# CO2_sensor_v1_1_print.net
KiCad netlist of a schematic drawn in EAGLE
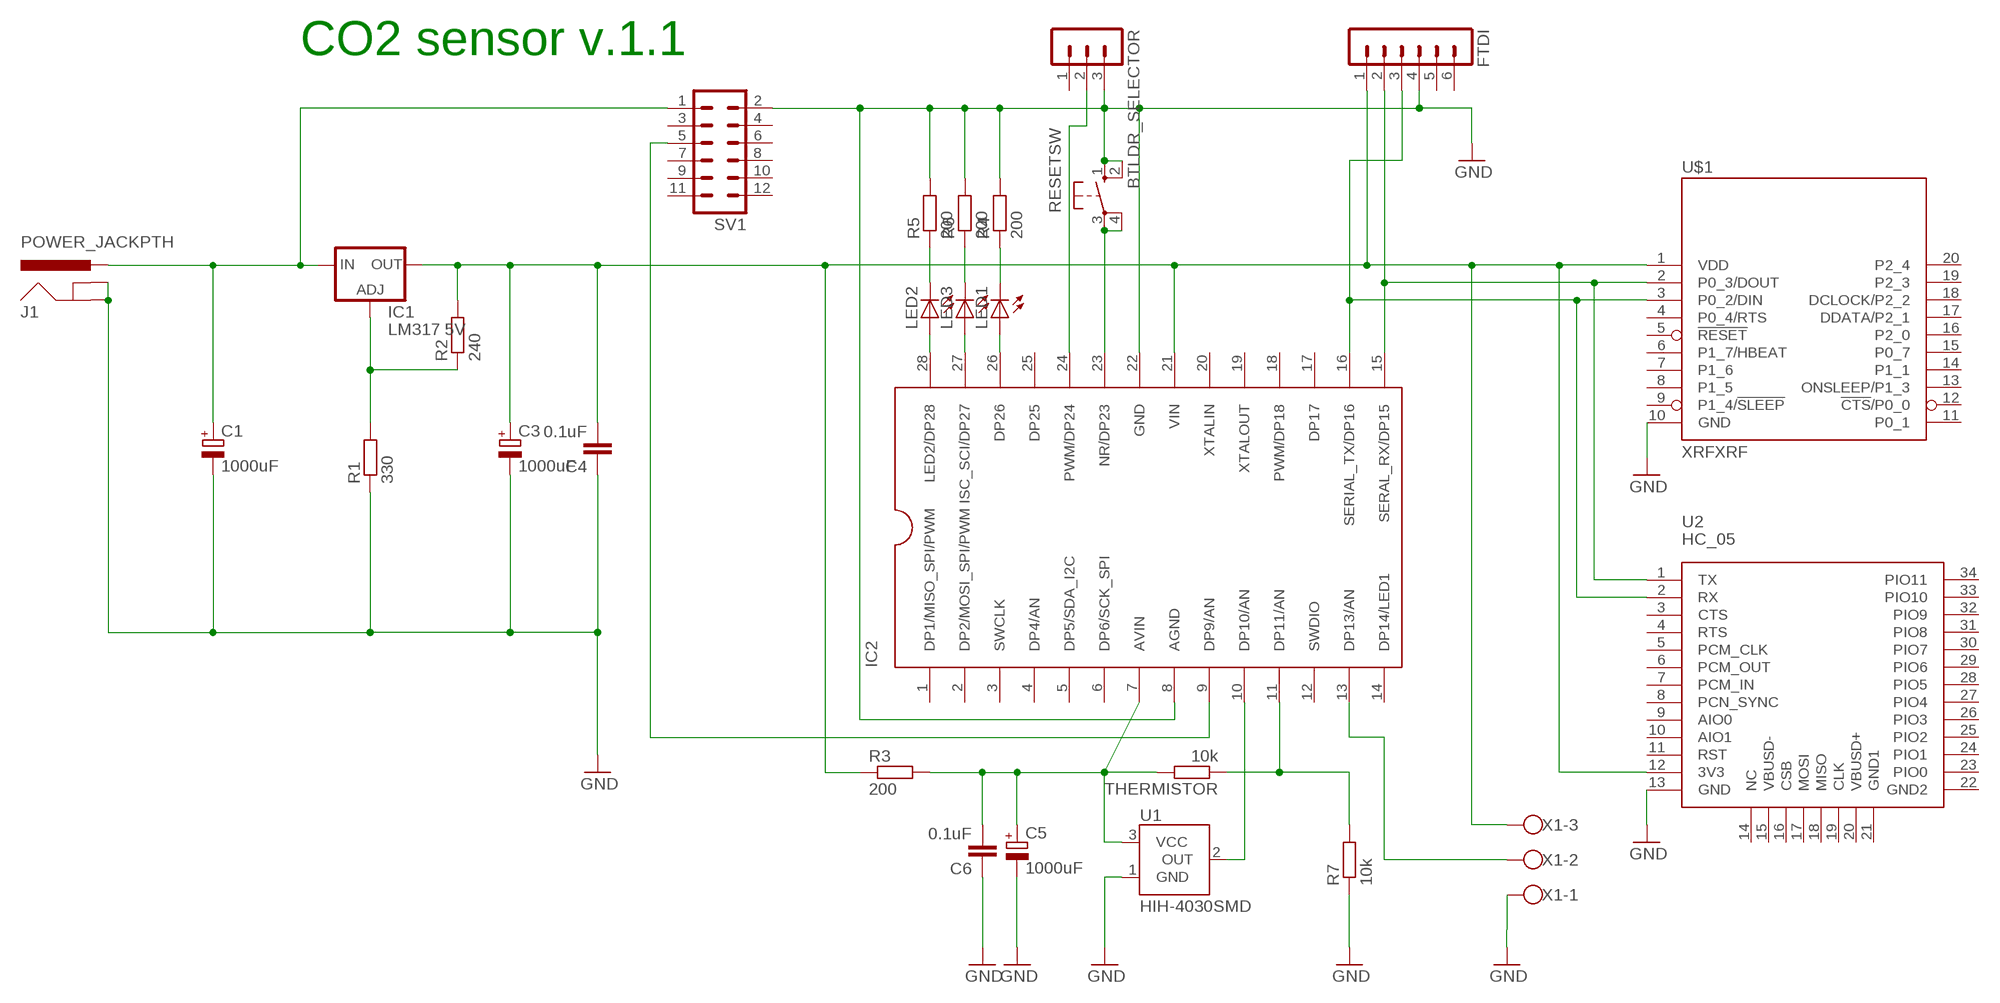
[diagram p0: schematic, sheet 1]

(export (version "E")
  (design (tool "Eeschema 10.0.6"))
  (components
    (comp (ref "BTLDR_SELECTOR")
      (value "MA03-1")
      (footprint "eagle-import:MA03-1")
      (libsource (lib "eagle-import") (part "MA03-1"))
    )
    (comp (ref "C1")
      (value "1000uF")
      (footprint "eagle-import:E5-10,5")
      (libsource (lib "eagle-import") (part "CPOL-EUE5-10.5"))
    )
    (comp (ref "C3")
      (value "1000uF")
      (footprint "eagle-import:E5-10,5")
      (libsource (lib "eagle-import") (part "CPOL-EUE5-10.5"))
    )
    (comp (ref "C4")
      (value "0.1uF")
      (footprint "eagle-import:C050-025X075")
      (libsource (lib "eagle-import") (part "C-EU050-025X075"))
    )
    (comp (ref "C5")
      (value "1000uF")
      (footprint "eagle-import:E5-10,5")
      (libsource (lib "eagle-import") (part "CPOL-EUE5-10.5"))
    )
    (comp (ref "C6")
      (value "0.1uF")
      (footprint "eagle-import:C050-025X075")
      (libsource (lib "eagle-import") (part "C-EU050-025X075"))
    )
    (comp (ref "FTDI")
      (value "MA06-1")
      (footprint "eagle-import:MA06-1")
      (libsource (lib "eagle-import") (part "MA06-1"))
    )
    (comp (ref "IC1")
      (value "LM317 5V")
      (footprint "eagle-import:317TL")
      (libsource (lib "eagle-import") (part "LM317TL"))
    )
    (comp (ref "IC2")
      (value "LPC1114FN28")
      (footprint "eagle-import:DIP28")
      (libsource (lib "eagle-import") (part "LPC1114FN28"))
    )
    (comp (ref "J1")
      (value "POWER_JACKPTH")
      (footprint "eagle-import:POWER_JACK_PTH")
      (libsource (lib "eagle-import") (part "POWER_JACKPTH"))
    )
    (comp (ref "LED1")
      (value "LED3MM")
      (footprint "eagle-import:LED3MM")
      (libsource (lib "eagle-import") (part "LED3MM"))
    )
    (comp (ref "LED2")
      (value "LED3MM")
      (footprint "eagle-import:LED3MM")
      (libsource (lib "eagle-import") (part "LED3MM"))
    )
    (comp (ref "LED3")
      (value "LED3MM")
      (footprint "eagle-import:LED3MM")
      (libsource (lib "eagle-import") (part "LED3MM"))
    )
    (comp (ref "R1")
      (value "330")
      (footprint "eagle-import:0207_10")
      (libsource (lib "eagle-import") (part "R-EU_0207/10"))
    )
    (comp (ref "R2")
      (value "240")
      (footprint "eagle-import:0207_12")
      (libsource (lib "eagle-import") (part "R-EU_0207/12"))
    )
    (comp (ref "R3")
      (value "200")
      (footprint "eagle-import:0207_12")
      (libsource (lib "eagle-import") (part "R-EU_0207/12"))
    )
    (comp (ref "R4")
      (value "200")
      (footprint "eagle-import:0207_10")
      (libsource (lib "eagle-import") (part "R-EU_0207/10"))
    )
    (comp (ref "R5")
      (value "200")
      (footprint "eagle-import:0207_2V")
      (libsource (lib "eagle-import") (part "R-EU_0207/2V"))
    )
    (comp (ref "R6")
      (value "200")
      (footprint "eagle-import:0207_12")
      (libsource (lib "eagle-import") (part "R-EU_0207/12"))
    )
    (comp (ref "R7")
      (value "10k")
      (footprint "eagle-import:0207_12")
      (libsource (lib "eagle-import") (part "R-EU_0207/12"))
    )
    (comp (ref "RESETSW")
      (value "10-XX")
      (footprint "eagle-import:B3F-10XX")
      (fields (field (name "MPN") "B3F-1000"))
      (libsource (lib "eagle-import") (part "10-XX"))
    )
    (comp (ref "SV1")
      (value "MA06-2")
      (footprint "eagle-import:MA06-2")
      (libsource (lib "eagle-import") (part "MA06-2"))
    )
    (comp (ref "THERMISTOR")
      (value "10k")
      (footprint "eagle-import:0207_5V")
      (libsource (lib "eagle-import") (part "R-EU_0207/5V"))
    )
    (comp (ref "U$1")
      (value "XRFXRF")
      (footprint "eagle-import:XRF")
      (libsource (lib "eagle-import") (part "XRFXRF"))
    )
    (comp (ref "U1")
      (value "HIH-4030SMD")
      (footprint "eagle-import:HIH-4030")
      (libsource (lib "eagle-import") (part "HIH-4030SMD"))
    )
    (comp (ref "U2")
      (value "HC_05")
      (footprint "eagle-import:BLUETOOTH_SMD")
      (libsource (lib "eagle-import") (part "HC_05"))
    )
    (comp (ref "X1")
      (value "W237-103")
      (footprint "eagle-import:W237-103")
      (fields (field (name "MPN") "237-103"))
      (libsource (lib "eagle-import") (part "W237-103"))
    )
  )
  (nets
    (net (code "1") (name "GND") (class "Default")
      (node (ref "BTLDR_SELECTOR") (pin "3") (pinfunction "3_3") (pintype "passive"))
      (node (ref "C1") (pin "-") (pinfunction "-_-") (pintype "passive"))
      (node (ref "C3") (pin "-") (pinfunction "-_-") (pintype "passive"))
      (node (ref "C4") (pin "1") (pinfunction "1_1") (pintype "passive"))
      (node (ref "C5") (pin "-") (pinfunction "-_-") (pintype "passive"))
      (node (ref "C6") (pin "1") (pinfunction "1_1") (pintype "passive"))
      (node (ref "FTDI") (pin "4") (pinfunction "4_4") (pintype "passive"))
      (node (ref "IC2") (pin "22") (pinfunction "GND_22") (pintype "power_in"))
      (node (ref "IC2") (pin "8") (pinfunction "AGND_8") (pintype "power_in"))
      (node (ref "J1") (pin "GND") (pinfunction "GND_GND") (pintype "bidirectional"))
      (node (ref "J1") (pin "GNDBREAK") (pinfunction "GNDBREAK_GNDBREAK") (pintype "bidirectional"))
      (node (ref "R1") (pin "1") (pinfunction "1_1") (pintype "passive"))
      (node (ref "R4") (pin "2") (pinfunction "2_2") (pintype "passive"))
      (node (ref "R5") (pin "2") (pinfunction "2_2") (pintype "passive"))
      (node (ref "R6") (pin "2") (pinfunction "2_2") (pintype "passive"))
      (node (ref "R7") (pin "1") (pinfunction "1_1") (pintype "passive"))
      (node (ref "RESETSW") (pin "1") (pinfunction "S_1") (pintype "passive"))
      (node (ref "RESETSW") (pin "2") (pinfunction "S1_2") (pintype "passive"))
      (node (ref "SV1") (pin "2") (pinfunction "2_2") (pintype "passive"))
      (node (ref "U$1") (pin "10") (pinfunction "GND_10") (pintype "power_in"))
      (node (ref "U1") (pin "1") (pinfunction "GND_1") (pintype "bidirectional"))
      (node (ref "U2") (pin "13") (pinfunction "GND_13") (pintype "bidirectional"))
      (node (ref "X1") (pin "1") (pinfunction "KL_1") (pintype "passive"))
    )
    (net (code "2") (name "Net-(IC1-ADJ)") (class "Default")
      (node (ref "IC1") (pin "1") (pinfunction "ADJ_1") (pintype "input"))
      (node (ref "R1") (pin "2") (pinfunction "2_2") (pintype "passive"))
      (node (ref "R2") (pin "1") (pinfunction "1_1") (pintype "passive"))
    )
    (net (code "3") (name "Net-(IC1-IN)") (class "Default")
      (node (ref "C1") (pin "+") (pinfunction "+_+") (pintype "passive"))
      (node (ref "IC1") (pin "3") (pinfunction "IN_3") (pintype "input"))
      (node (ref "J1") (pin "PWR") (pinfunction "PWR_PWR") (pintype "bidirectional"))
      (node (ref "SV1") (pin "1") (pinfunction "1_1") (pintype "passive"))
    )
    (net (code "4") (name "Net-(IC1-OUT)") (class "Default")
      (node (ref "C3") (pin "+") (pinfunction "+_+") (pintype "passive"))
      (node (ref "C4") (pin "2") (pinfunction "2_2") (pintype "passive"))
      (node (ref "FTDI") (pin "1") (pinfunction "1_1") (pintype "passive"))
      (node (ref "IC1") (pin "2") (pinfunction "OUT_2") (pintype "passive"))
      (node (ref "IC2") (pin "21") (pinfunction "VIN_21") (pintype "power_in"))
      (node (ref "R2") (pin "2") (pinfunction "2_2") (pintype "passive"))
      (node (ref "R3") (pin "1") (pinfunction "1_1") (pintype "passive"))
      (node (ref "U$1") (pin "1") (pinfunction "VDD_1") (pintype "power_in"))
      (node (ref "U2") (pin "12") (pinfunction "3V3_12") (pintype "bidirectional"))
      (node (ref "X1") (pin "3") (pinfunction "KL_3") (pintype "passive"))
    )
    (net (code "5") (name "Net-(IC2-AVIN)") (class "Default")
      (node (ref "C5") (pin "+") (pinfunction "+_+") (pintype "passive"))
      (node (ref "C6") (pin "2") (pinfunction "2_2") (pintype "passive"))
      (node (ref "IC2") (pin "7") (pinfunction "AVIN_7") (pintype "power_in"))
      (node (ref "R3") (pin "2") (pinfunction "2_2") (pintype "passive"))
      (node (ref "THERMISTOR") (pin "2") (pinfunction "2_2") (pintype "passive"))
      (node (ref "U1") (pin "3") (pinfunction "VCC_3") (pintype "bidirectional"))
    )
    (net (code "6") (name "Net-(IC2-DP9{slash}AN)") (class "Default")
      (node (ref "IC2") (pin "9") (pinfunction "DP9/AN_9") (pintype "bidirectional"))
      (node (ref "SV1") (pin "5") (pinfunction "5_5") (pintype "passive"))
    )
    (net (code "7") (name "Net-(IC2-DP10{slash}AN)") (class "Default")
      (node (ref "IC2") (pin "10") (pinfunction "DP10/AN_10") (pintype "bidirectional"))
      (node (ref "U1") (pin "2") (pinfunction "OUT_2") (pintype "bidirectional"))
    )
    (net (code "8") (name "Net-(IC2-DP11{slash}AN)") (class "Default")
      (node (ref "IC2") (pin "11") (pinfunction "DP11/AN_11") (pintype "bidirectional"))
      (node (ref "R7") (pin "2") (pinfunction "2_2") (pintype "passive"))
      (node (ref "THERMISTOR") (pin "1") (pinfunction "1_1") (pintype "passive"))
    )
    (net (code "9") (name "Net-(IC2-DP13{slash}AN)") (class "Default")
      (node (ref "IC2") (pin "13") (pinfunction "DP13/AN_13") (pintype "bidirectional"))
      (node (ref "X1") (pin "2") (pinfunction "KL_2") (pintype "passive"))
    )
    (net (code "10") (name "Net-(IC2-DP26)") (class "Default")
      (node (ref "IC2") (pin "26") (pinfunction "DP26_26") (pintype "bidirectional"))
      (node (ref "LED1") (pin "A") (pinfunction "A_A") (pintype "passive"))
    )
    (net (code "11") (name "Net-(IC2-ISC_SCI{slash}DP27)") (class "Default")
      (node (ref "IC2") (pin "27") (pinfunction "ISC_SCI/DP27_27") (pintype "bidirectional"))
      (node (ref "LED3") (pin "A") (pinfunction "A_A") (pintype "passive"))
    )
    (net (code "12") (name "Net-(IC2-LED2{slash}DP28)") (class "Default")
      (node (ref "IC2") (pin "28") (pinfunction "LED2/DP28_28") (pintype "bidirectional"))
      (node (ref "LED2") (pin "A") (pinfunction "A_A") (pintype "passive"))
    )
    (net (code "13") (name "Net-(IC2-NR{slash}DP23)") (class "Default")
      (node (ref "IC2") (pin "23") (pinfunction "NR/DP23_23") (pintype "bidirectional"))
      (node (ref "RESETSW") (pin "3") (pinfunction "P_3") (pintype "passive"))
      (node (ref "RESETSW") (pin "4") (pinfunction "P1_4") (pintype "passive"))
    )
    (net (code "14") (name "Net-(IC2-PWM{slash}DP24)") (class "Default")
      (node (ref "BTLDR_SELECTOR") (pin "2") (pinfunction "2_2") (pintype "passive"))
      (node (ref "IC2") (pin "24") (pinfunction "PWM/DP24_24") (pintype "bidirectional"))
    )
    (net (code "15") (name "Net-(IC2-SERAL_RX{slash}DP15)") (class "Default")
      (node (ref "FTDI") (pin "2") (pinfunction "2_2") (pintype "passive"))
      (node (ref "IC2") (pin "15") (pinfunction "SERAL_RX/DP15_15") (pintype "bidirectional"))
      (node (ref "U$1") (pin "2") (pinfunction "P0_3/DOUT_2") (pintype "output"))
      (node (ref "U2") (pin "1") (pinfunction "TX_1") (pintype "bidirectional"))
    )
    (net (code "16") (name "Net-(IC2-SERIAL_TX{slash}DP16)") (class "Default")
      (node (ref "FTDI") (pin "3") (pinfunction "3_3") (pintype "passive"))
      (node (ref "IC2") (pin "16") (pinfunction "SERIAL_TX/DP16_16") (pintype "bidirectional"))
      (node (ref "U$1") (pin "3") (pinfunction "P0_2/DIN_3") (pintype "input"))
      (node (ref "U2") (pin "2") (pinfunction "RX_2") (pintype "bidirectional"))
    )
    (net (code "17") (name "Net-(LED1-C)") (class "Default")
      (node (ref "LED1") (pin "K") (pinfunction "C_K") (pintype "passive"))
      (node (ref "R4") (pin "1") (pinfunction "1_1") (pintype "passive"))
    )
    (net (code "18") (name "Net-(LED2-C)") (class "Default")
      (node (ref "LED2") (pin "K") (pinfunction "C_K") (pintype "passive"))
      (node (ref "R5") (pin "1") (pinfunction "1_1") (pintype "passive"))
    )
    (net (code "19") (name "Net-(LED3-C)") (class "Default")
      (node (ref "LED3") (pin "K") (pinfunction "C_K") (pintype "passive"))
      (node (ref "R6") (pin "1") (pinfunction "1_1") (pintype "passive"))
    )
    (net (code "20") (name "unconnected-(BTLDR_SELECTOR-Pad1)") (class "Default")
      (node (ref "BTLDR_SELECTOR") (pin "1") (pinfunction "1_1") (pintype "passive"))
    )
    (net (code "21") (name "unconnected-(FTDI-Pad5)") (class "Default")
      (node (ref "FTDI") (pin "5") (pinfunction "5_5") (pintype "passive"))
    )
    (net (code "22") (name "unconnected-(FTDI-Pad6)") (class "Default")
      (node (ref "FTDI") (pin "6") (pinfunction "6_6") (pintype "passive"))
    )
    (net (code "23") (name "unconnected-(IC2-DP1{slash}MISO_SPI{slash}PWM-Pad1)") (class "Default")
      (node (ref "IC2") (pin "1") (pinfunction "DP1/MISO_SPI/PWM_1") (pintype "bidirectional"))
    )
    (net (code "24") (name "unconnected-(IC2-DP2{slash}MOSI_SPI{slash}PWM-Pad2)") (class "Default")
      (node (ref "IC2") (pin "2") (pinfunction "DP2/MOSI_SPI/PWM_2") (pintype "bidirectional"))
    )
    (net (code "25") (name "unconnected-(IC2-DP4{slash}AN-Pad4)") (class "Default")
      (node (ref "IC2") (pin "4") (pinfunction "DP4/AN_4") (pintype "bidirectional"))
    )
    (net (code "26") (name "unconnected-(IC2-DP5{slash}SDA_I2C-Pad5)") (class "Default")
      (node (ref "IC2") (pin "5") (pinfunction "DP5/SDA_I2C_5") (pintype "bidirectional"))
    )
    (net (code "27") (name "unconnected-(IC2-DP6{slash}SCK_SPI-Pad6)") (class "Default")
      (node (ref "IC2") (pin "6") (pinfunction "DP6/SCK_SPI_6") (pintype "bidirectional"))
    )
    (net (code "28") (name "unconnected-(IC2-DP14{slash}LED1-Pad14)") (class "Default")
      (node (ref "IC2") (pin "14") (pinfunction "DP14/LED1_14") (pintype "bidirectional"))
    )
    (net (code "29") (name "unconnected-(IC2-DP17-Pad17)") (class "Default")
      (node (ref "IC2") (pin "17") (pinfunction "DP17_17") (pintype "bidirectional"))
    )
    (net (code "30") (name "unconnected-(IC2-DP25-Pad25)") (class "Default")
      (node (ref "IC2") (pin "25") (pinfunction "DP25_25") (pintype "bidirectional"))
    )
    (net (code "31") (name "unconnected-(IC2-PWM{slash}DP18-Pad18)") (class "Default")
      (node (ref "IC2") (pin "18") (pinfunction "PWM/DP18_18") (pintype "bidirectional"))
    )
    (net (code "32") (name "unconnected-(IC2-SWCLK-Pad3)") (class "Default")
      (node (ref "IC2") (pin "3") (pinfunction "SWCLK_3") (pintype "bidirectional"))
    )
    (net (code "33") (name "unconnected-(IC2-SWDIO-Pad12)") (class "Default")
      (node (ref "IC2") (pin "12") (pinfunction "SWDIO_12") (pintype "bidirectional"))
    )
    (net (code "34") (name "unconnected-(IC2-XTALIN-Pad20)") (class "Default")
      (node (ref "IC2") (pin "20") (pinfunction "XTALIN_20") (pintype "input"))
    )
    (net (code "35") (name "unconnected-(IC2-XTALOUT-Pad19)") (class "Default")
      (node (ref "IC2") (pin "19") (pinfunction "XTALOUT_19") (pintype "output"))
    )
    (net (code "36") (name "unconnected-(SV1-Pad3)") (class "Default")
      (node (ref "SV1") (pin "3") (pinfunction "3_3") (pintype "passive"))
    )
    (net (code "37") (name "unconnected-(SV1-Pad4)") (class "Default")
      (node (ref "SV1") (pin "4") (pinfunction "4_4") (pintype "passive"))
    )
    (net (code "38") (name "unconnected-(SV1-Pad6)") (class "Default")
      (node (ref "SV1") (pin "6") (pinfunction "6_6") (pintype "passive"))
    )
    (net (code "39") (name "unconnected-(SV1-Pad7)") (class "Default")
      (node (ref "SV1") (pin "7") (pinfunction "7_7") (pintype "passive"))
    )
    (net (code "40") (name "unconnected-(SV1-Pad8)") (class "Default")
      (node (ref "SV1") (pin "8") (pinfunction "8_8") (pintype "passive"))
    )
    (net (code "41") (name "unconnected-(SV1-Pad9)") (class "Default")
      (node (ref "SV1") (pin "9") (pinfunction "9_9") (pintype "passive"))
    )
    (net (code "42") (name "unconnected-(SV1-Pad10)") (class "Default")
      (node (ref "SV1") (pin "10") (pinfunction "10_10") (pintype "passive"))
    )
    (net (code "43") (name "unconnected-(SV1-Pad11)") (class "Default")
      (node (ref "SV1") (pin "11") (pinfunction "11_11") (pintype "passive"))
    )
    (net (code "44") (name "unconnected-(SV1-Pad12)") (class "Default")
      (node (ref "SV1") (pin "12") (pinfunction "12_12") (pintype "passive"))
    )
    (net (code "45") (name "unconnected-(U$1-DCLOCK{slash}P2_2-Pad18)") (class "Default")
      (node (ref "U$1") (pin "18") (pinfunction "DCLOCK/P2_2_18") (pintype "bidirectional"))
    )
    (net (code "46") (name "unconnected-(U$1-DDATA{slash}P2_1-Pad17)") (class "Default")
      (node (ref "U$1") (pin "17") (pinfunction "DDATA/P2_1_17") (pintype "bidirectional"))
    )
    (net (code "47") (name "unconnected-(U$1-ONSLEEP{slash}P1_3-Pad13)") (class "Default")
      (node (ref "U$1") (pin "13") (pinfunction "ONSLEEP/P1_3_13") (pintype "bidirectional"))
    )
    (net (code "48") (name "unconnected-(U$1-P0_1-Pad11)") (class "Default")
      (node (ref "U$1") (pin "11") (pinfunction "P0_1_11") (pintype "bidirectional"))
    )
    (net (code "49") (name "unconnected-(U$1-P0_4{slash}RTS-Pad4)") (class "Default")
      (node (ref "U$1") (pin "4") (pinfunction "P0_4/RTS_4") (pintype "bidirectional"))
    )
    (net (code "50") (name "unconnected-(U$1-P0_7-Pad15)") (class "Default")
      (node (ref "U$1") (pin "15") (pinfunction "P0_7_15") (pintype "bidirectional"))
    )
    (net (code "51") (name "unconnected-(U$1-P1_1-Pad14)") (class "Default")
      (node (ref "U$1") (pin "14") (pinfunction "P1_1_14") (pintype "bidirectional"))
    )
    (net (code "52") (name "unconnected-(U$1-P1_4{slash}~{SLEEP}-Pad9)") (class "Default")
      (node (ref "U$1") (pin "9") (pinfunction "P1_4/~{SLEEP}_9") (pintype "bidirectional"))
    )
    (net (code "53") (name "unconnected-(U$1-P1_5-Pad8)") (class "Default")
      (node (ref "U$1") (pin "8") (pinfunction "P1_5_8") (pintype "bidirectional"))
    )
    (net (code "54") (name "unconnected-(U$1-P1_6-Pad7)") (class "Default")
      (node (ref "U$1") (pin "7") (pinfunction "P1_6_7") (pintype "bidirectional"))
    )
    (net (code "55") (name "unconnected-(U$1-P1_7{slash}HBEAT-Pad6)") (class "Default")
      (node (ref "U$1") (pin "6") (pinfunction "P1_7/HBEAT_6") (pintype "bidirectional"))
    )
    (net (code "56") (name "unconnected-(U$1-P2_0-Pad16)") (class "Default")
      (node (ref "U$1") (pin "16") (pinfunction "P2_0_16") (pintype "input"))
    )
    (net (code "57") (name "unconnected-(U$1-P2_3-Pad19)") (class "Default")
      (node (ref "U$1") (pin "19") (pinfunction "P2_3_19") (pintype "bidirectional"))
    )
    (net (code "58") (name "unconnected-(U$1-P2_4-Pad20)") (class "Default")
      (node (ref "U$1") (pin "20") (pinfunction "P2_4_20") (pintype "bidirectional"))
    )
    (net (code "59") (name "unconnected-(U$1-~{CTS}{slash}P0_0-Pad12)") (class "Default")
      (node (ref "U$1") (pin "12") (pinfunction "~{CTS}/P0_0_12") (pintype "output"))
    )
    (net (code "60") (name "unconnected-(U$1-~{RESET}-Pad5)") (class "Default")
      (node (ref "U$1") (pin "5") (pinfunction "~{RESET}_5") (pintype "input"))
    )
    (net (code "61") (name "unconnected-(U2-AIO0-Pad9)") (class "Default")
      (node (ref "U2") (pin "9") (pinfunction "AIO0_9") (pintype "bidirectional"))
    )
    (net (code "62") (name "unconnected-(U2-AIO1-Pad10)") (class "Default")
      (node (ref "U2") (pin "10") (pinfunction "AIO1_10") (pintype "bidirectional"))
    )
    (net (code "63") (name "unconnected-(U2-CLK-Pad19)") (class "Default")
      (node (ref "U2") (pin "19") (pinfunction "CLK_19") (pintype "bidirectional"))
    )
    (net (code "64") (name "unconnected-(U2-CSB-Pad16)") (class "Default")
      (node (ref "U2") (pin "16") (pinfunction "CSB_16") (pintype "bidirectional"))
    )
    (net (code "65") (name "unconnected-(U2-CTS-Pad3)") (class "Default")
      (node (ref "U2") (pin "3") (pinfunction "CTS_3") (pintype "bidirectional"))
    )
    (net (code "66") (name "unconnected-(U2-GND1-Pad21)") (class "Default")
      (node (ref "U2") (pin "21") (pinfunction "GND1_21") (pintype "bidirectional"))
    )
    (net (code "67") (name "unconnected-(U2-GND2-Pad22)") (class "Default")
      (node (ref "U2") (pin "22") (pinfunction "GND2_22") (pintype "bidirectional"))
    )
    (net (code "68") (name "unconnected-(U2-MISO-Pad18)") (class "Default")
      (node (ref "U2") (pin "18") (pinfunction "MISO_18") (pintype "bidirectional"))
    )
    (net (code "69") (name "unconnected-(U2-MOSI-Pad17)") (class "Default")
      (node (ref "U2") (pin "17") (pinfunction "MOSI_17") (pintype "bidirectional"))
    )
    (net (code "70") (name "unconnected-(U2-NC-Pad14)") (class "Default")
      (node (ref "U2") (pin "14") (pinfunction "NC_14") (pintype "bidirectional"))
    )
    (net (code "71") (name "unconnected-(U2-PCM_CLK-Pad5)") (class "Default")
      (node (ref "U2") (pin "5") (pinfunction "PCM_CLK_5") (pintype "bidirectional"))
    )
    (net (code "72") (name "unconnected-(U2-PCM_IN-Pad7)") (class "Default")
      (node (ref "U2") (pin "7") (pinfunction "PCM_IN_7") (pintype "bidirectional"))
    )
    (net (code "73") (name "unconnected-(U2-PCM_OUT-Pad6)") (class "Default")
      (node (ref "U2") (pin "6") (pinfunction "PCM_OUT_6") (pintype "bidirectional"))
    )
    (net (code "74") (name "unconnected-(U2-PCN_SYNC-Pad8)") (class "Default")
      (node (ref "U2") (pin "8") (pinfunction "PCN_SYNC_8") (pintype "bidirectional"))
    )
    (net (code "75") (name "unconnected-(U2-PIO0-Pad23)") (class "Default")
      (node (ref "U2") (pin "23") (pinfunction "PIO0_23") (pintype "bidirectional"))
    )
    (net (code "76") (name "unconnected-(U2-PIO1-Pad24)") (class "Default")
      (node (ref "U2") (pin "24") (pinfunction "PIO1_24") (pintype "bidirectional"))
    )
    (net (code "77") (name "unconnected-(U2-PIO2-Pad25)") (class "Default")
      (node (ref "U2") (pin "25") (pinfunction "PIO2_25") (pintype "bidirectional"))
    )
    (net (code "78") (name "unconnected-(U2-PIO3-Pad26)") (class "Default")
      (node (ref "U2") (pin "26") (pinfunction "PIO3_26") (pintype "bidirectional"))
    )
    (net (code "79") (name "unconnected-(U2-PIO4-Pad27)") (class "Default")
      (node (ref "U2") (pin "27") (pinfunction "PIO4_27") (pintype "bidirectional"))
    )
    (net (code "80") (name "unconnected-(U2-PIO5-Pad28)") (class "Default")
      (node (ref "U2") (pin "28") (pinfunction "PIO5_28") (pintype "bidirectional"))
    )
    (net (code "81") (name "unconnected-(U2-PIO6-Pad29)") (class "Default")
      (node (ref "U2") (pin "29") (pinfunction "PIO6_29") (pintype "bidirectional"))
    )
    (net (code "82") (name "unconnected-(U2-PIO7-Pad30)") (class "Default")
      (node (ref "U2") (pin "30") (pinfunction "PIO7_30") (pintype "bidirectional"))
    )
    (net (code "83") (name "unconnected-(U2-PIO8-Pad31)") (class "Default")
      (node (ref "U2") (pin "31") (pinfunction "PIO8_31") (pintype "bidirectional"))
    )
    (net (code "84") (name "unconnected-(U2-PIO9-Pad32)") (class "Default")
      (node (ref "U2") (pin "32") (pinfunction "PIO9_32") (pintype "bidirectional"))
    )
    (net (code "85") (name "unconnected-(U2-PIO10-Pad33)") (class "Default")
      (node (ref "U2") (pin "33") (pinfunction "PIO10_33") (pintype "bidirectional"))
    )
    (net (code "86") (name "unconnected-(U2-PIO11-Pad34)") (class "Default")
      (node (ref "U2") (pin "34") (pinfunction "PIO11_34") (pintype "bidirectional"))
    )
    (net (code "87") (name "unconnected-(U2-RST-Pad11)") (class "Default")
      (node (ref "U2") (pin "11") (pinfunction "RST_11") (pintype "bidirectional"))
    )
    (net (code "88") (name "unconnected-(U2-RTS-Pad4)") (class "Default")
      (node (ref "U2") (pin "4") (pinfunction "RTS_4") (pintype "bidirectional"))
    )
    (net (code "89") (name "unconnected-(U2-VBUSD+-Pad20)") (class "Default")
      (node (ref "U2") (pin "20") (pinfunction "VBUSD+_20") (pintype "bidirectional"))
    )
    (net (code "90") (name "unconnected-(U2-VBUSD--Pad15)") (class "Default")
      (node (ref "U2") (pin "15") (pinfunction "VBUSD-_15") (pintype "bidirectional"))
    )
  )
)
